# ReaXtrobe.net
KiCad netlist of a schematic drawn in EAGLE
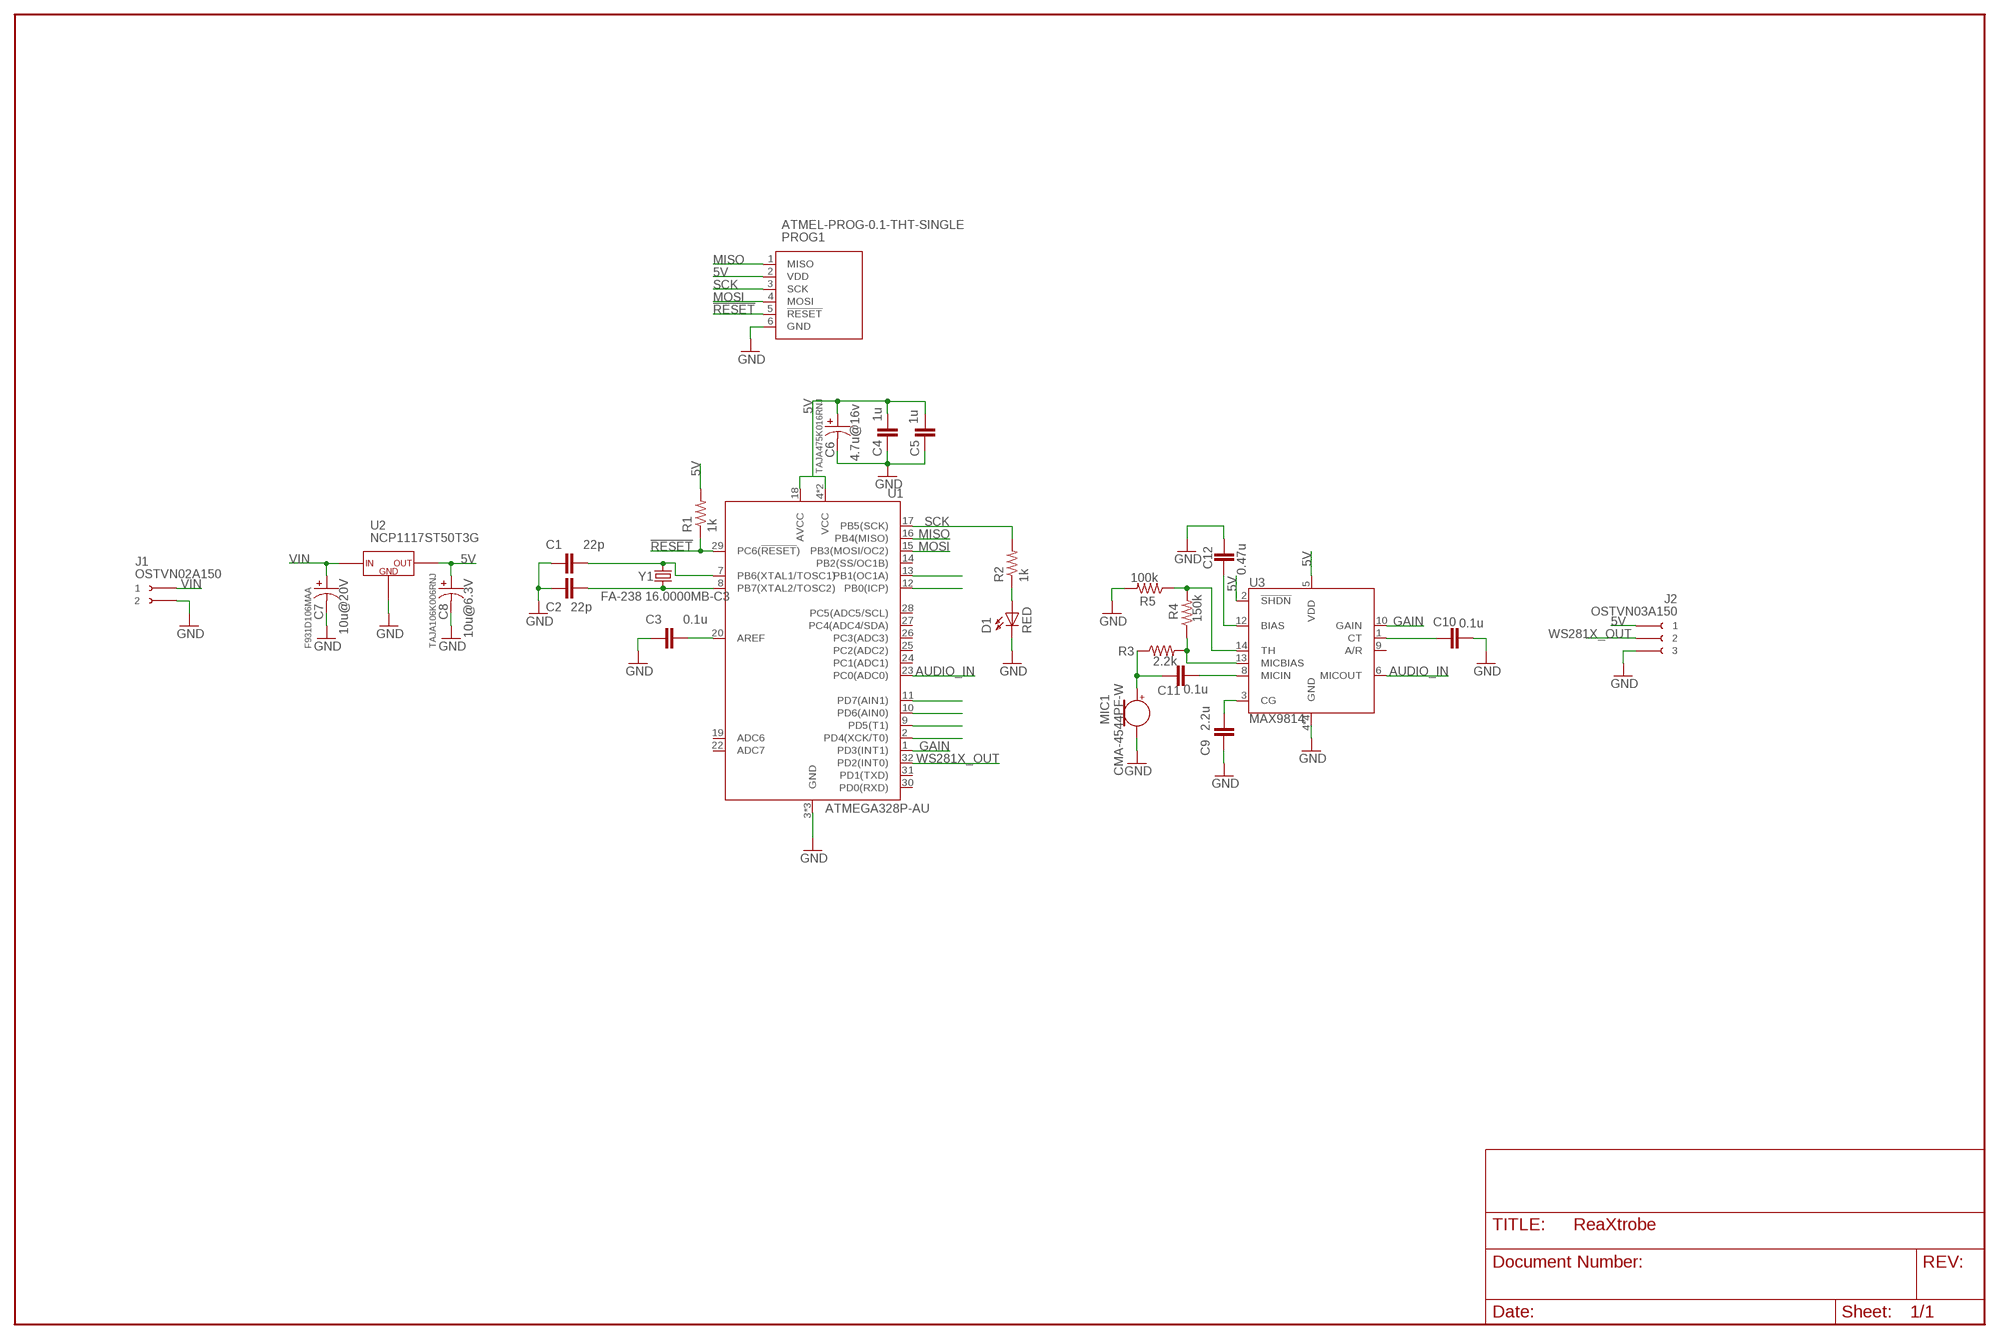
[diagram p0: schematic, sheet 1]

(export (version "E")
  (design (tool "Eeschema 10.0.6"))
  (components
    (comp (ref "C1")
      (value "22p")
      (footprint "eagle-import:C0603")
      (libsource (lib "eagle-import") (part "CAP-CER-SMD0603"))
    )
    (comp (ref "C2")
      (value "22p")
      (footprint "eagle-import:C0603")
      (libsource (lib "eagle-import") (part "CAP-CER-SMD0603"))
    )
    (comp (ref "C3")
      (value "0.1u")
      (footprint "eagle-import:C0603")
      (libsource (lib "eagle-import") (part "CAP-CER-SMD0603"))
    )
    (comp (ref "C4")
      (value "1u")
      (footprint "eagle-import:C0603")
      (libsource (lib "eagle-import") (part "CAP-CER-SMD0603"))
    )
    (comp (ref "C5")
      (value "1u")
      (footprint "eagle-import:C0603")
      (libsource (lib "eagle-import") (part "CAP-CER-SMD0603"))
    )
    (comp (ref "C6")
      (value "4.7u@16v")
      (footprint "eagle-import:CAPMP3216X160")
      (libsource (lib "eagle-import") (part "CAP-TANT-SMD1206"))
    )
    (comp (ref "C7")
      (value "10u@20V")
      (footprint "eagle-import:CAPMP3216X160")
      (libsource (lib "eagle-import") (part "CAP-TANT-SMD1206"))
    )
    (comp (ref "C8")
      (value "10u@6.3V")
      (footprint "eagle-import:CAPMP3216X160")
      (libsource (lib "eagle-import") (part "CAP-TANT-SMD1206"))
    )
    (comp (ref "C9")
      (value "2.2u")
      (footprint "eagle-import:C0603")
      (libsource (lib "eagle-import") (part "CAP-CER-SMD0603"))
    )
    (comp (ref "C10")
      (value "0.1u")
      (footprint "eagle-import:C0603")
      (libsource (lib "eagle-import") (part "CAP-CER-SMD0603"))
    )
    (comp (ref "C11")
      (value "0.1u")
      (footprint "eagle-import:C0603")
      (libsource (lib "eagle-import") (part "CAP-CER-SMD0603"))
    )
    (comp (ref "C12")
      (value "0.47u")
      (footprint "eagle-import:C0603")
      (libsource (lib "eagle-import") (part "CAP-CER-SMD0603"))
    )
    (comp (ref "D1")
      (value "RED")
      (footprint "eagle-import:CHIP-LED0603")
      (libsource (lib "eagle-import") (part "LED-0603"))
    )
    (comp (ref "J1")
      (value "OSTVN02A150")
      (footprint "eagle-import:OSTVN02A150")
      (libsource (lib "eagle-import") (part "OSTVN02A150"))
    )
    (comp (ref "J2")
      (value "OSTVN03A150")
      (footprint "eagle-import:OSTVN03A150")
      (libsource (lib "eagle-import") (part "OSTVN03A150"))
    )
    (comp (ref "MIC1")
      (value "CMA-4544PF-W")
      (footprint "eagle-import:MIC_CMA-4544PF-W")
      (libsource (lib "eagle-import") (part "CMA-4544PF-W"))
    )
    (comp (ref "PROG1")
      (value "ATMEL-PROG-0.1-THT-SINGLE")
      (footprint "eagle-import:HEADER-0.1-6")
      (libsource (lib "eagle-import") (part "ATMEL-PROG-0.1-THT-SINGLE"))
    )
    (comp (ref "R1")
      (value "1k")
      (footprint "eagle-import:R0603")
      (libsource (lib "eagle-import") (part "RES-SMD0603"))
    )
    (comp (ref "R2")
      (value "1k")
      (footprint "eagle-import:R0603")
      (libsource (lib "eagle-import") (part "RES-SMD0603"))
    )
    (comp (ref "R3")
      (value "2.2k")
      (footprint "eagle-import:R0603")
      (libsource (lib "eagle-import") (part "RES-SMD0603"))
    )
    (comp (ref "R4")
      (value "150k")
      (footprint "eagle-import:R0603")
      (libsource (lib "eagle-import") (part "RES-SMD0603"))
    )
    (comp (ref "R5")
      (value "100k")
      (footprint "eagle-import:R0603")
      (libsource (lib "eagle-import") (part "RES-SMD0603"))
    )
    (comp (ref "U1")
      (value "ATMEGA328P-AU")
      (footprint "eagle-import:QFP80P900X900X120-32")
      (libsource (lib "eagle-import") (part "ATMEGA328P-AU"))
    )
    (comp (ref "U2")
      (value "NCP1117ST50T3G")
      (footprint "eagle-import:SOT223")
      (libsource (lib "eagle-import") (part "NCP1117ST50T3G"))
    )
    (comp (ref "U3")
      (value "MAX9814")
      (footprint "eagle-import:SON40P300X300X80-15T170X230")
      (libsource (lib "eagle-import") (part "MAX9814"))
    )
    (comp (ref "Y1")
      (value "FA-238 16.0000MB-C3")
      (footprint "eagle-import:OSCCC320X250X70")
      (libsource (lib "eagle-import") (part "CRYSTAL-SMD-43.2X2.5L"))
    )
  )
  (nets
    (net (code "1") (name "/5V") (class "Default")
      (node (ref "C4") (pin "2") (pinfunction "2_2") (pintype "passive"))
      (node (ref "C5") (pin "2") (pinfunction "2_2") (pintype "passive"))
      (node (ref "C6") (pin "A") (pinfunction "A_A") (pintype "passive"))
      (node (ref "C8") (pin "A") (pinfunction "A_A") (pintype "passive"))
      (node (ref "J2") (pin "P$1") (pinfunction "1_P$1") (pintype "passive"))
      (node (ref "PROG1") (pin "2") (pinfunction "VDD_2") (pintype "passive"))
      (node (ref "R1") (pin "2") (pinfunction "2_2") (pintype "passive"))
      (node (ref "U1") (pin "18") (pinfunction "AVCC_18") (pintype "passive"))
      (node (ref "U1") (pin "4") (pinfunction "VCC_4") (pintype "passive"))
      (node (ref "U1") (pin "6") (pinfunction "VCC_6") (pintype "passive"))
      (node (ref "U2") (pin "2") (pinfunction "OUT_2") (pintype "passive"))
      (node (ref "U3") (pin "2") (pinfunction "~{SHDN}_2") (pintype "passive"))
      (node (ref "U3") (pin "5") (pinfunction "VDD_5") (pintype "passive"))
    )
    (net (code "2") (name "/AUDIO_IN") (class "Default")
      (node (ref "U1") (pin "23") (pinfunction "PC0(ADC0)_23") (pintype "passive"))
      (node (ref "U3") (pin "6") (pinfunction "MICOUT_6") (pintype "passive"))
    )
    (net (code "3") (name "/GAIN") (class "Default")
      (node (ref "U1") (pin "1") (pinfunction "PD3(INT1)_1") (pintype "passive"))
      (node (ref "U3") (pin "10") (pinfunction "GAIN_10") (pintype "passive"))
    )
    (net (code "4") (name "/MISO") (class "Default")
      (node (ref "PROG1") (pin "1") (pinfunction "MISO_1") (pintype "passive"))
      (node (ref "U1") (pin "16") (pinfunction "PB4(MISO)_16") (pintype "passive"))
    )
    (net (code "5") (name "/MOSI") (class "Default")
      (node (ref "PROG1") (pin "4") (pinfunction "MOSI_4") (pintype "passive"))
      (node (ref "U1") (pin "15") (pinfunction "PB3(MOSI/OC2)_15") (pintype "passive"))
    )
    (net (code "6") (name "/SCK") (class "Default")
      (node (ref "PROG1") (pin "3") (pinfunction "SCK_3") (pintype "passive"))
      (node (ref "R2") (pin "2") (pinfunction "2_2") (pintype "passive"))
      (node (ref "U1") (pin "17") (pinfunction "PB5(SCK)_17") (pintype "passive"))
    )
    (net (code "7") (name "/VIN") (class "Default")
      (node (ref "C7") (pin "A") (pinfunction "A_A") (pintype "passive"))
      (node (ref "J1") (pin "P$1") (pinfunction "1_P$1") (pintype "passive"))
      (node (ref "U2") (pin "3") (pinfunction "IN_3") (pintype "passive"))
    )
    (net (code "8") (name "/WS281X_OUT") (class "Default")
      (node (ref "J2") (pin "P$2") (pinfunction "2_P$2") (pintype "passive"))
      (node (ref "U1") (pin "32") (pinfunction "PD2(INT0)_32") (pintype "passive"))
    )
    (net (code "9") (name "/~{RESET}") (class "Default")
      (node (ref "PROG1") (pin "5") (pinfunction "~{RESET}_5") (pintype "passive"))
      (node (ref "R1") (pin "1") (pinfunction "1_1") (pintype "passive"))
      (node (ref "U1") (pin "29") (pinfunction "PC6(~{RESET})_29") (pintype "passive"))
    )
    (net (code "10") (name "GND") (class "Default")
      (node (ref "C1") (pin "1") (pinfunction "1_1") (pintype "passive"))
      (node (ref "C10") (pin "1") (pinfunction "1_1") (pintype "passive"))
      (node (ref "C12") (pin "1") (pinfunction "1_1") (pintype "passive"))
      (node (ref "C2") (pin "1") (pinfunction "1_1") (pintype "passive"))
      (node (ref "C3") (pin "1") (pinfunction "1_1") (pintype "passive"))
      (node (ref "C4") (pin "1") (pinfunction "1_1") (pintype "passive"))
      (node (ref "C5") (pin "1") (pinfunction "1_1") (pintype "passive"))
      (node (ref "C6") (pin "C") (pinfunction "C_C") (pintype "passive"))
      (node (ref "C7") (pin "C") (pinfunction "C_C") (pintype "passive"))
      (node (ref "C8") (pin "C") (pinfunction "C_C") (pintype "passive"))
      (node (ref "C9") (pin "1") (pinfunction "1_1") (pintype "passive"))
      (node (ref "D1") (pin "C") (pinfunction "K_C") (pintype "passive"))
      (node (ref "J1") (pin "P$2") (pinfunction "2_P$2") (pintype "passive"))
      (node (ref "J2") (pin "P$3") (pinfunction "3_P$3") (pintype "passive"))
      (node (ref "MIC1") (pin "2") (pinfunction "N_2") (pintype "passive"))
      (node (ref "PROG1") (pin "6") (pinfunction "GND_6") (pintype "passive"))
      (node (ref "R5") (pin "2") (pinfunction "2_2") (pintype "passive"))
      (node (ref "U1") (pin "21") (pinfunction "GND_21") (pintype "passive"))
      (node (ref "U1") (pin "3") (pinfunction "GND_3") (pintype "passive"))
      (node (ref "U1") (pin "5") (pinfunction "GND_5") (pintype "passive"))
      (node (ref "U2") (pin "1") (pinfunction "GND_1") (pintype "passive"))
      (node (ref "U3") (pin "11") (pinfunction "GND_11") (pintype "passive"))
      (node (ref "U3") (pin "15") (pinfunction "GND_15") (pintype "passive"))
      (node (ref "U3") (pin "4") (pinfunction "GND_4") (pintype "passive"))
      (node (ref "U3") (pin "7") (pinfunction "GND_7") (pintype "passive"))
    )
    (net (code "11") (name "Net-(D1-PadA)") (class "Default")
      (node (ref "D1") (pin "A") (pinfunction "A_A") (pintype "passive"))
      (node (ref "R2") (pin "1") (pinfunction "1_1") (pintype "passive"))
    )
    (net (code "12") (name "Net-(MIC1-P)") (class "Default")
      (node (ref "C11") (pin "2") (pinfunction "2_2") (pintype "passive"))
      (node (ref "MIC1") (pin "1") (pinfunction "P_1") (pintype "passive"))
      (node (ref "R3") (pin "1") (pinfunction "1_1") (pintype "passive"))
    )
    (net (code "13") (name "Net-(U1-AREF)") (class "Default")
      (node (ref "C3") (pin "2") (pinfunction "2_2") (pintype "passive"))
      (node (ref "U1") (pin "20") (pinfunction "AREF_20") (pintype "passive"))
    )
    (net (code "14") (name "Net-(U1-PB6(XTAL1{slash}TOSC1))") (class "Default")
      (node (ref "C1") (pin "2") (pinfunction "2_2") (pintype "passive"))
      (node (ref "U1") (pin "7") (pinfunction "PB6(XTAL1/TOSC1)_7") (pintype "passive"))
      (node (ref "Y1") (pin "3") (pinfunction "2_3") (pintype "passive"))
    )
    (net (code "15") (name "Net-(U1-PB7(XTAL2{slash}TOSC2))") (class "Default")
      (node (ref "C2") (pin "2") (pinfunction "2_2") (pintype "passive"))
      (node (ref "U1") (pin "8") (pinfunction "PB7(XTAL2/TOSC2)_8") (pintype "passive"))
      (node (ref "Y1") (pin "1") (pinfunction "1_1") (pintype "passive"))
    )
    (net (code "16") (name "Net-(U3-BIAS)") (class "Default")
      (node (ref "C12") (pin "2") (pinfunction "2_2") (pintype "passive"))
      (node (ref "U3") (pin "12") (pinfunction "BIAS_12") (pintype "passive"))
    )
    (net (code "17") (name "Net-(U3-CG)") (class "Default")
      (node (ref "C9") (pin "2") (pinfunction "2_2") (pintype "passive"))
      (node (ref "U3") (pin "3") (pinfunction "CG_3") (pintype "passive"))
    )
    (net (code "18") (name "Net-(U3-CT)") (class "Default")
      (node (ref "C10") (pin "2") (pinfunction "2_2") (pintype "passive"))
      (node (ref "U3") (pin "1") (pinfunction "CT_1") (pintype "passive"))
    )
    (net (code "19") (name "Net-(U3-MICBIAS)") (class "Default")
      (node (ref "R3") (pin "2") (pinfunction "2_2") (pintype "passive"))
      (node (ref "R4") (pin "1") (pinfunction "1_1") (pintype "passive"))
      (node (ref "U3") (pin "13") (pinfunction "MICBIAS_13") (pintype "passive"))
    )
    (net (code "20") (name "Net-(U3-MICIN)") (class "Default")
      (node (ref "C11") (pin "1") (pinfunction "1_1") (pintype "passive"))
      (node (ref "U3") (pin "8") (pinfunction "MICIN_8") (pintype "passive"))
    )
    (net (code "21") (name "Net-(U3-TH)") (class "Default")
      (node (ref "R4") (pin "2") (pinfunction "2_2") (pintype "passive"))
      (node (ref "R5") (pin "1") (pinfunction "1_1") (pintype "passive"))
      (node (ref "U3") (pin "14") (pinfunction "TH_14") (pintype "passive"))
    )
    (net (code "22") (name "unconnected-(U1-ADC6-Pad19)") (class "Default")
      (node (ref "U1") (pin "19") (pinfunction "ADC6_19") (pintype "passive"))
    )
    (net (code "23") (name "unconnected-(U1-ADC7-Pad22)") (class "Default")
      (node (ref "U1") (pin "22") (pinfunction "ADC7_22") (pintype "passive"))
    )
    (net (code "24") (name "unconnected-(U1-PB0(ICP)-Pad12)") (class "Default")
      (node (ref "U1") (pin "12") (pinfunction "PB0(ICP)_12") (pintype "passive"))
    )
    (net (code "25") (name "unconnected-(U1-PB1(OC1A)-Pad13)") (class "Default")
      (node (ref "U1") (pin "13") (pinfunction "PB1(OC1A)_13") (pintype "passive"))
    )
    (net (code "26") (name "unconnected-(U1-PB2(SS{slash}OC1B)-Pad14)") (class "Default")
      (node (ref "U1") (pin "14") (pinfunction "PB2(SS/OC1B)_14") (pintype "passive"))
    )
    (net (code "27") (name "unconnected-(U1-PC1(ADC1)-Pad24)") (class "Default")
      (node (ref "U1") (pin "24") (pinfunction "PC1(ADC1)_24") (pintype "passive"))
    )
    (net (code "28") (name "unconnected-(U1-PC2(ADC2)-Pad25)") (class "Default")
      (node (ref "U1") (pin "25") (pinfunction "PC2(ADC2)_25") (pintype "passive"))
    )
    (net (code "29") (name "unconnected-(U1-PC3(ADC3)-Pad26)") (class "Default")
      (node (ref "U1") (pin "26") (pinfunction "PC3(ADC3)_26") (pintype "passive"))
    )
    (net (code "30") (name "unconnected-(U1-PC4(ADC4{slash}SDA)-Pad27)") (class "Default")
      (node (ref "U1") (pin "27") (pinfunction "PC4(ADC4/SDA)_27") (pintype "passive"))
    )
    (net (code "31") (name "unconnected-(U1-PC5(ADC5{slash}SCL)-Pad28)") (class "Default")
      (node (ref "U1") (pin "28") (pinfunction "PC5(ADC5/SCL)_28") (pintype "passive"))
    )
    (net (code "32") (name "unconnected-(U1-PD0(RXD)-Pad30)") (class "Default")
      (node (ref "U1") (pin "30") (pinfunction "PD0(RXD)_30") (pintype "passive"))
    )
    (net (code "33") (name "unconnected-(U1-PD1(TXD)-Pad31)") (class "Default")
      (node (ref "U1") (pin "31") (pinfunction "PD1(TXD)_31") (pintype "passive"))
    )
    (net (code "34") (name "unconnected-(U1-PD4(XCK{slash}T0)-Pad2)") (class "Default")
      (node (ref "U1") (pin "2") (pinfunction "PD4(XCK/T0)_2") (pintype "passive"))
    )
    (net (code "35") (name "unconnected-(U1-PD5(T1)-Pad9)") (class "Default")
      (node (ref "U1") (pin "9") (pinfunction "PD5(T1)_9") (pintype "passive"))
    )
    (net (code "36") (name "unconnected-(U1-PD6(AIN0)-Pad10)") (class "Default")
      (node (ref "U1") (pin "10") (pinfunction "PD6(AIN0)_10") (pintype "passive"))
    )
    (net (code "37") (name "unconnected-(U1-PD7(AIN1)-Pad11)") (class "Default")
      (node (ref "U1") (pin "11") (pinfunction "PD7(AIN1)_11") (pintype "passive"))
    )
    (net (code "38") (name "unconnected-(U3-A{slash}R-Pad9)") (class "Default")
      (node (ref "U3") (pin "9") (pinfunction "A/R_9") (pintype "passive"))
    )
  )
)
